# jkff_v8.net
KiCad netlist of a schematic drawn in EAGLE
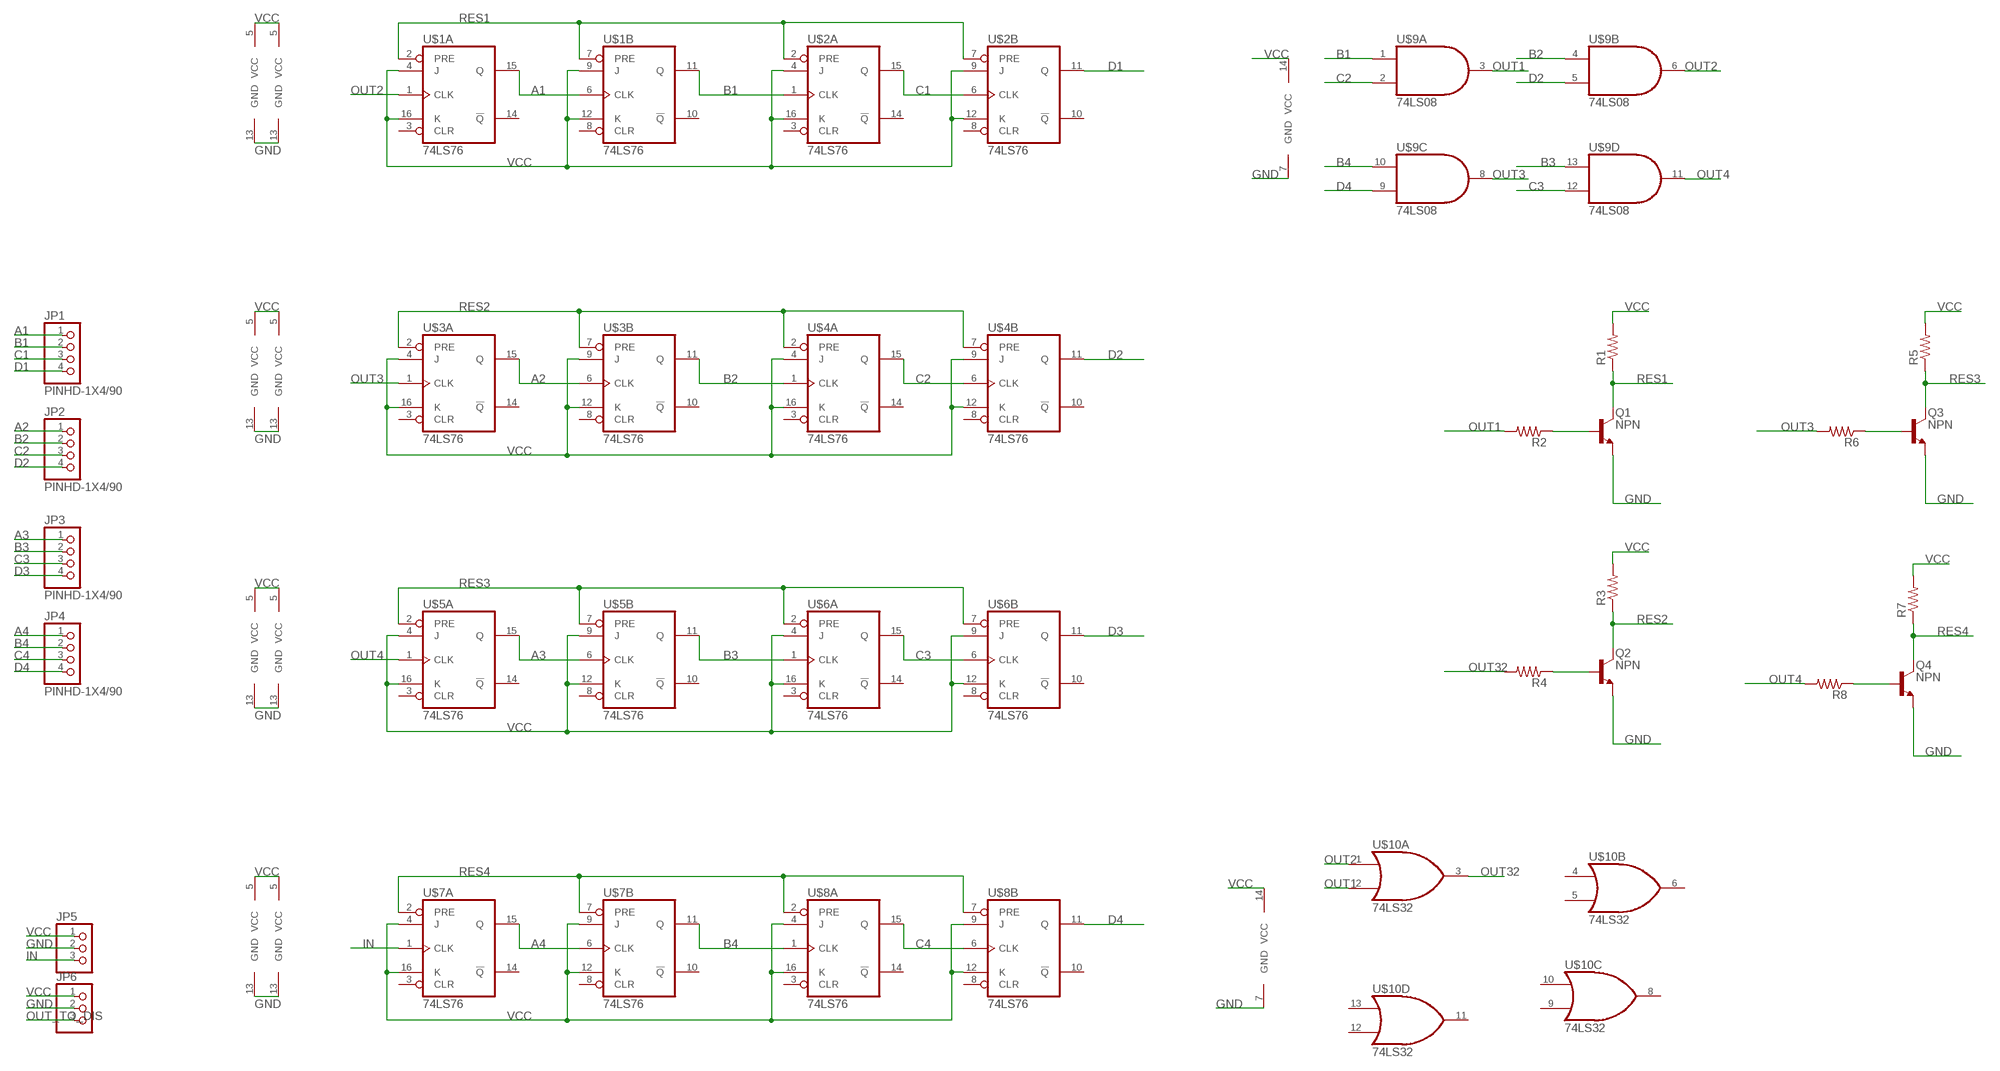
[diagram p0: schematic, sheet 1]

(export (version "E")
  (design (tool "Eeschema 10.0.6"))
  (components
    (comp (ref "JP1")
      (value "PINHD-1X4/90")
      (footprint "eagle-import:1X04_90")
      (libsource (lib "eagle-import") (part "PINHD-1X4/90"))
    )
    (comp (ref "JP2")
      (value "PINHD-1X4/90")
      (footprint "eagle-import:1X04_90")
      (libsource (lib "eagle-import") (part "PINHD-1X4/90"))
    )
    (comp (ref "JP3")
      (value "PINHD-1X4/90")
      (footprint "eagle-import:1X04_90")
      (libsource (lib "eagle-import") (part "PINHD-1X4/90"))
    )
    (comp (ref "JP4")
      (value "PINHD-1X4/90")
      (footprint "eagle-import:1X04_90")
      (libsource (lib "eagle-import") (part "PINHD-1X4/90"))
    )
    (comp (ref "JP5")
      (value "PINHD-1X3CB")
      (footprint "eagle-import:1X03-CLEANBIG")
      (libsource (lib "eagle-import") (part "PINHD-1X3CB"))
    )
    (comp (ref "JP6")
      (value "PINHD-1X3CB")
      (footprint "eagle-import:1X03-CLEANBIG")
      (libsource (lib "eagle-import") (part "PINHD-1X3CB"))
    )
    (comp (ref "Q1")
      (value "NPN")
      (footprint "eagle-import:TO92")
      (libsource (lib "eagle-import") (part "NPNTO92-EBC_"))
    )
    (comp (ref "Q2")
      (value "NPN")
      (footprint "eagle-import:TO92")
      (libsource (lib "eagle-import") (part "NPNTO92-EBC_"))
    )
    (comp (ref "Q3")
      (value "NPN")
      (footprint "eagle-import:TO92")
      (libsource (lib "eagle-import") (part "NPNTO92-EBC_"))
    )
    (comp (ref "Q4")
      (value "NPN")
      (footprint "eagle-import:TO92")
      (libsource (lib "eagle-import") (part "NPNTO92-EBC_"))
    )
    (comp (ref "R1")
      (value "R-US_AXIAL-7.2MM-PITCH")
      (footprint "eagle-import:RESAD724W46L381D178B")
      (libsource (lib "eagle-import") (part "R-USAXIAL-7.2MM-PITCH_"))
    )
    (comp (ref "R2")
      (value "R-US_AXIAL-7.2MM-PITCH")
      (footprint "eagle-import:RESAD724W46L381D178B")
      (libsource (lib "eagle-import") (part "R-USAXIAL-7.2MM-PITCH_"))
    )
    (comp (ref "R3")
      (value "R-US_AXIAL-7.2MM-PITCH")
      (footprint "eagle-import:RESAD724W46L381D178B")
      (libsource (lib "eagle-import") (part "R-USAXIAL-7.2MM-PITCH_"))
    )
    (comp (ref "R4")
      (value "R-US_AXIAL-7.2MM-PITCH")
      (footprint "eagle-import:RESAD724W46L381D178B")
      (libsource (lib "eagle-import") (part "R-USAXIAL-7.2MM-PITCH_"))
    )
    (comp (ref "R5")
      (value "R-US_AXIAL-7.2MM-PITCH")
      (footprint "eagle-import:RESAD724W46L381D178B")
      (libsource (lib "eagle-import") (part "R-USAXIAL-7.2MM-PITCH_"))
    )
    (comp (ref "R6")
      (value "R-US_AXIAL-7.2MM-PITCH")
      (footprint "eagle-import:RESAD724W46L381D178B")
      (libsource (lib "eagle-import") (part "R-USAXIAL-7.2MM-PITCH_"))
    )
    (comp (ref "R7")
      (value "R-US_AXIAL-7.2MM-PITCH")
      (footprint "eagle-import:RESAD724W46L381D178B")
      (libsource (lib "eagle-import") (part "R-USAXIAL-7.2MM-PITCH_"))
    )
    (comp (ref "R8")
      (value "R-US_AXIAL-7.2MM-PITCH")
      (footprint "eagle-import:RESAD724W46L381D178B")
      (libsource (lib "eagle-import") (part "R-USAXIAL-7.2MM-PITCH_"))
    )
    (comp (ref "U$1")
      (value "74LS76")
      (footprint "eagle-import:DIO16")
      (libsource (lib "eagle-import") (part "74LS76"))
    )
    (comp (ref "U$2")
      (value "74LS76")
      (footprint "eagle-import:DIO16")
      (libsource (lib "eagle-import") (part "74LS76"))
    )
    (comp (ref "U$3")
      (value "74LS76")
      (footprint "eagle-import:DIO16")
      (libsource (lib "eagle-import") (part "74LS76"))
    )
    (comp (ref "U$4")
      (value "74LS76")
      (footprint "eagle-import:DIO16")
      (libsource (lib "eagle-import") (part "74LS76"))
    )
    (comp (ref "U$5")
      (value "74LS76")
      (footprint "eagle-import:DIO16")
      (libsource (lib "eagle-import") (part "74LS76"))
    )
    (comp (ref "U$6")
      (value "74LS76")
      (footprint "eagle-import:DIO16")
      (libsource (lib "eagle-import") (part "74LS76"))
    )
    (comp (ref "U$7")
      (value "74LS76")
      (footprint "eagle-import:DIO16")
      (libsource (lib "eagle-import") (part "74LS76"))
    )
    (comp (ref "U$8")
      (value "74LS76")
      (footprint "eagle-import:DIO16")
      (libsource (lib "eagle-import") (part "74LS76"))
    )
    (comp (ref "U$9")
      (value "74LS08")
      (footprint "eagle-import:DIO14")
      (libsource (lib "eagle-import") (part "74LS08"))
    )
    (comp (ref "U$10")
      (value "74LS32")
      (footprint "eagle-import:DIO14")
      (libsource (lib "eagle-import") (part "74LS32"))
    )
  )
  (nets
    (net (code "1") (name "/A1") (class "Default")
      (node (ref "JP1") (pin "1") (pinfunction "1_1") (pintype "passive"))
      (node (ref "U$1") (pin "15") (pinfunction "Q_15") (pintype "output"))
      (node (ref "U$1") (pin "6") (pinfunction "CLK_6") (pintype "input"))
    )
    (net (code "2") (name "/A2") (class "Default")
      (node (ref "JP2") (pin "1") (pinfunction "1_1") (pintype "passive"))
      (node (ref "U$3") (pin "15") (pinfunction "Q_15") (pintype "output"))
      (node (ref "U$3") (pin "6") (pinfunction "CLK_6") (pintype "input"))
    )
    (net (code "3") (name "/A3") (class "Default")
      (node (ref "JP3") (pin "1") (pinfunction "1_1") (pintype "passive"))
      (node (ref "U$5") (pin "15") (pinfunction "Q_15") (pintype "output"))
      (node (ref "U$5") (pin "6") (pinfunction "CLK_6") (pintype "input"))
    )
    (net (code "4") (name "/A4") (class "Default")
      (node (ref "JP4") (pin "1") (pinfunction "1_1") (pintype "passive"))
      (node (ref "U$7") (pin "15") (pinfunction "Q_15") (pintype "output"))
      (node (ref "U$7") (pin "6") (pinfunction "CLK_6") (pintype "input"))
    )
    (net (code "5") (name "/B1") (class "Default")
      (node (ref "JP1") (pin "2") (pinfunction "2_2") (pintype "passive"))
      (node (ref "U$1") (pin "11") (pinfunction "Q_11") (pintype "output"))
      (node (ref "U$2") (pin "1") (pinfunction "CLK_1") (pintype "input"))
      (node (ref "U$9") (pin "1") (pinfunction "I0_1") (pintype "input"))
    )
    (net (code "6") (name "/B2") (class "Default")
      (node (ref "JP2") (pin "2") (pinfunction "2_2") (pintype "passive"))
      (node (ref "U$3") (pin "11") (pinfunction "Q_11") (pintype "output"))
      (node (ref "U$4") (pin "1") (pinfunction "CLK_1") (pintype "input"))
      (node (ref "U$9") (pin "4") (pinfunction "I0_4") (pintype "input"))
    )
    (net (code "7") (name "/B3") (class "Default")
      (node (ref "JP3") (pin "2") (pinfunction "2_2") (pintype "passive"))
      (node (ref "U$5") (pin "11") (pinfunction "Q_11") (pintype "output"))
      (node (ref "U$6") (pin "1") (pinfunction "CLK_1") (pintype "input"))
      (node (ref "U$9") (pin "13") (pinfunction "I0_13") (pintype "input"))
    )
    (net (code "8") (name "/B4") (class "Default")
      (node (ref "JP4") (pin "2") (pinfunction "2_2") (pintype "passive"))
      (node (ref "U$7") (pin "11") (pinfunction "Q_11") (pintype "output"))
      (node (ref "U$8") (pin "1") (pinfunction "CLK_1") (pintype "input"))
      (node (ref "U$9") (pin "10") (pinfunction "I0_10") (pintype "input"))
    )
    (net (code "9") (name "/C1") (class "Default")
      (node (ref "JP1") (pin "3") (pinfunction "3_3") (pintype "passive"))
      (node (ref "U$2") (pin "15") (pinfunction "Q_15") (pintype "output"))
      (node (ref "U$2") (pin "6") (pinfunction "CLK_6") (pintype "input"))
    )
    (net (code "10") (name "/C2") (class "Default")
      (node (ref "JP2") (pin "3") (pinfunction "3_3") (pintype "passive"))
      (node (ref "U$4") (pin "15") (pinfunction "Q_15") (pintype "output"))
      (node (ref "U$4") (pin "6") (pinfunction "CLK_6") (pintype "input"))
      (node (ref "U$9") (pin "2") (pinfunction "I1_2") (pintype "input"))
    )
    (net (code "11") (name "/C3") (class "Default")
      (node (ref "JP3") (pin "3") (pinfunction "3_3") (pintype "passive"))
      (node (ref "U$6") (pin "15") (pinfunction "Q_15") (pintype "output"))
      (node (ref "U$6") (pin "6") (pinfunction "CLK_6") (pintype "input"))
      (node (ref "U$9") (pin "12") (pinfunction "I1_12") (pintype "input"))
    )
    (net (code "12") (name "/C4") (class "Default")
      (node (ref "JP4") (pin "3") (pinfunction "3_3") (pintype "passive"))
      (node (ref "U$8") (pin "15") (pinfunction "Q_15") (pintype "output"))
      (node (ref "U$8") (pin "6") (pinfunction "CLK_6") (pintype "input"))
    )
    (net (code "13") (name "/D1") (class "Default")
      (node (ref "JP1") (pin "4") (pinfunction "4_4") (pintype "passive"))
      (node (ref "U$2") (pin "11") (pinfunction "Q_11") (pintype "output"))
    )
    (net (code "14") (name "/D2") (class "Default")
      (node (ref "JP2") (pin "4") (pinfunction "4_4") (pintype "passive"))
      (node (ref "U$4") (pin "11") (pinfunction "Q_11") (pintype "output"))
      (node (ref "U$9") (pin "5") (pinfunction "I1_5") (pintype "input"))
    )
    (net (code "15") (name "/D3") (class "Default")
      (node (ref "JP3") (pin "4") (pinfunction "4_4") (pintype "passive"))
      (node (ref "U$6") (pin "11") (pinfunction "Q_11") (pintype "output"))
    )
    (net (code "16") (name "/D4") (class "Default")
      (node (ref "JP4") (pin "4") (pinfunction "4_4") (pintype "passive"))
      (node (ref "U$8") (pin "11") (pinfunction "Q_11") (pintype "output"))
      (node (ref "U$9") (pin "9") (pinfunction "I1_9") (pintype "input"))
    )
    (net (code "17") (name "/GND") (class "Default")
      (node (ref "JP5") (pin "2") (pinfunction "2_2") (pintype "passive"))
      (node (ref "JP6") (pin "2") (pinfunction "2_2") (pintype "passive"))
      (node (ref "Q1") (pin "1") (pinfunction "E_1") (pintype "passive"))
      (node (ref "Q2") (pin "1") (pinfunction "E_1") (pintype "passive"))
      (node (ref "Q3") (pin "1") (pinfunction "E_1") (pintype "passive"))
      (node (ref "Q4") (pin "1") (pinfunction "E_1") (pintype "passive"))
      (node (ref "U$1") (pin "13") (pinfunction "GND_13") (pintype "bidirectional"))
      (node (ref "U$10") (pin "7") (pinfunction "GND_7") (pintype "bidirectional"))
      (node (ref "U$2") (pin "13") (pinfunction "GND_13") (pintype "bidirectional"))
      (node (ref "U$3") (pin "13") (pinfunction "GND_13") (pintype "bidirectional"))
      (node (ref "U$4") (pin "13") (pinfunction "GND_13") (pintype "bidirectional"))
      (node (ref "U$5") (pin "13") (pinfunction "GND_13") (pintype "bidirectional"))
      (node (ref "U$6") (pin "13") (pinfunction "GND_13") (pintype "bidirectional"))
      (node (ref "U$7") (pin "13") (pinfunction "GND_13") (pintype "bidirectional"))
      (node (ref "U$8") (pin "13") (pinfunction "GND_13") (pintype "bidirectional"))
      (node (ref "U$9") (pin "7") (pinfunction "GND_7") (pintype "bidirectional"))
    )
    (net (code "18") (name "/IN") (class "Default")
      (node (ref "JP5") (pin "3") (pinfunction "3_3") (pintype "passive"))
      (node (ref "U$7") (pin "1") (pinfunction "CLK_1") (pintype "input"))
    )
    (net (code "19") (name "/OUT1") (class "Default")
      (node (ref "R2") (pin "2") (pinfunction "2_2") (pintype "passive"))
      (node (ref "U$10") (pin "2") (pinfunction "I1_2") (pintype "input"))
      (node (ref "U$9") (pin "3") (pinfunction "O_3") (pintype "output"))
    )
    (net (code "20") (name "/OUT2") (class "Default")
      (node (ref "U$1") (pin "1") (pinfunction "CLK_1") (pintype "input"))
      (node (ref "U$10") (pin "1") (pinfunction "I0_1") (pintype "input"))
      (node (ref "U$9") (pin "6") (pinfunction "O_6") (pintype "output"))
    )
    (net (code "21") (name "/OUT3") (class "Default")
      (node (ref "R6") (pin "2") (pinfunction "2_2") (pintype "passive"))
      (node (ref "U$3") (pin "1") (pinfunction "CLK_1") (pintype "input"))
      (node (ref "U$9") (pin "8") (pinfunction "O_8") (pintype "output"))
    )
    (net (code "22") (name "/OUT4") (class "Default")
      (node (ref "R8") (pin "2") (pinfunction "2_2") (pintype "passive"))
      (node (ref "U$5") (pin "1") (pinfunction "CLK_1") (pintype "input"))
      (node (ref "U$9") (pin "11") (pinfunction "O_11") (pintype "output"))
    )
    (net (code "23") (name "/OUT32") (class "Default")
      (node (ref "R4") (pin "2") (pinfunction "2_2") (pintype "passive"))
      (node (ref "U$10") (pin "3") (pinfunction "O_3") (pintype "output"))
    )
    (net (code "24") (name "/OUT_TO_DIS") (class "Default")
      (node (ref "JP6") (pin "3") (pinfunction "3_3") (pintype "passive"))
    )
    (net (code "25") (name "/RES1") (class "Default")
      (node (ref "Q1") (pin "3") (pinfunction "C_3") (pintype "passive"))
      (node (ref "R1") (pin "1") (pinfunction "1_1") (pintype "passive"))
      (node (ref "U$1") (pin "2") (pinfunction "PRE_2") (pintype "input"))
      (node (ref "U$1") (pin "7") (pinfunction "PRE_7") (pintype "input"))
      (node (ref "U$2") (pin "2") (pinfunction "PRE_2") (pintype "input"))
      (node (ref "U$2") (pin "7") (pinfunction "PRE_7") (pintype "input"))
    )
    (net (code "26") (name "/RES2") (class "Default")
      (node (ref "Q2") (pin "3") (pinfunction "C_3") (pintype "passive"))
      (node (ref "R3") (pin "1") (pinfunction "1_1") (pintype "passive"))
      (node (ref "U$3") (pin "2") (pinfunction "PRE_2") (pintype "input"))
      (node (ref "U$3") (pin "7") (pinfunction "PRE_7") (pintype "input"))
      (node (ref "U$4") (pin "2") (pinfunction "PRE_2") (pintype "input"))
      (node (ref "U$4") (pin "7") (pinfunction "PRE_7") (pintype "input"))
    )
    (net (code "27") (name "/RES3") (class "Default")
      (node (ref "Q3") (pin "3") (pinfunction "C_3") (pintype "passive"))
      (node (ref "R5") (pin "1") (pinfunction "1_1") (pintype "passive"))
      (node (ref "U$5") (pin "2") (pinfunction "PRE_2") (pintype "input"))
      (node (ref "U$5") (pin "7") (pinfunction "PRE_7") (pintype "input"))
      (node (ref "U$6") (pin "2") (pinfunction "PRE_2") (pintype "input"))
      (node (ref "U$6") (pin "7") (pinfunction "PRE_7") (pintype "input"))
    )
    (net (code "28") (name "/RES4") (class "Default")
      (node (ref "Q4") (pin "3") (pinfunction "C_3") (pintype "passive"))
      (node (ref "R7") (pin "1") (pinfunction "1_1") (pintype "passive"))
      (node (ref "U$7") (pin "2") (pinfunction "PRE_2") (pintype "input"))
      (node (ref "U$7") (pin "7") (pinfunction "PRE_7") (pintype "input"))
      (node (ref "U$8") (pin "2") (pinfunction "PRE_2") (pintype "input"))
      (node (ref "U$8") (pin "7") (pinfunction "PRE_7") (pintype "input"))
    )
    (net (code "29") (name "/VCC") (class "Default")
      (node (ref "JP5") (pin "1") (pinfunction "1_1") (pintype "passive"))
      (node (ref "JP6") (pin "1") (pinfunction "1_1") (pintype "passive"))
      (node (ref "R1") (pin "2") (pinfunction "2_2") (pintype "passive"))
      (node (ref "R3") (pin "2") (pinfunction "2_2") (pintype "passive"))
      (node (ref "R5") (pin "2") (pinfunction "2_2") (pintype "passive"))
      (node (ref "R7") (pin "2") (pinfunction "2_2") (pintype "passive"))
      (node (ref "U$1") (pin "12") (pinfunction "K_12") (pintype "input"))
      (node (ref "U$1") (pin "16") (pinfunction "K_16") (pintype "input"))
      (node (ref "U$1") (pin "4") (pinfunction "J_4") (pintype "input"))
      (node (ref "U$1") (pin "5") (pinfunction "VCC_5") (pintype "bidirectional"))
      (node (ref "U$1") (pin "9") (pinfunction "J_9") (pintype "input"))
      (node (ref "U$10") (pin "14") (pinfunction "VCC_14") (pintype "bidirectional"))
      (node (ref "U$2") (pin "12") (pinfunction "K_12") (pintype "input"))
      (node (ref "U$2") (pin "16") (pinfunction "K_16") (pintype "input"))
      (node (ref "U$2") (pin "4") (pinfunction "J_4") (pintype "input"))
      (node (ref "U$2") (pin "5") (pinfunction "VCC_5") (pintype "bidirectional"))
      (node (ref "U$2") (pin "9") (pinfunction "J_9") (pintype "input"))
      (node (ref "U$3") (pin "12") (pinfunction "K_12") (pintype "input"))
      (node (ref "U$3") (pin "16") (pinfunction "K_16") (pintype "input"))
      (node (ref "U$3") (pin "4") (pinfunction "J_4") (pintype "input"))
      (node (ref "U$3") (pin "5") (pinfunction "VCC_5") (pintype "bidirectional"))
      (node (ref "U$3") (pin "9") (pinfunction "J_9") (pintype "input"))
      (node (ref "U$4") (pin "12") (pinfunction "K_12") (pintype "input"))
      (node (ref "U$4") (pin "16") (pinfunction "K_16") (pintype "input"))
      (node (ref "U$4") (pin "4") (pinfunction "J_4") (pintype "input"))
      (node (ref "U$4") (pin "5") (pinfunction "VCC_5") (pintype "bidirectional"))
      (node (ref "U$4") (pin "9") (pinfunction "J_9") (pintype "input"))
      (node (ref "U$5") (pin "12") (pinfunction "K_12") (pintype "input"))
      (node (ref "U$5") (pin "16") (pinfunction "K_16") (pintype "input"))
      (node (ref "U$5") (pin "4") (pinfunction "J_4") (pintype "input"))
      (node (ref "U$5") (pin "5") (pinfunction "VCC_5") (pintype "bidirectional"))
      (node (ref "U$5") (pin "9") (pinfunction "J_9") (pintype "input"))
      (node (ref "U$6") (pin "12") (pinfunction "K_12") (pintype "input"))
      (node (ref "U$6") (pin "16") (pinfunction "K_16") (pintype "input"))
      (node (ref "U$6") (pin "4") (pinfunction "J_4") (pintype "input"))
      (node (ref "U$6") (pin "5") (pinfunction "VCC_5") (pintype "bidirectional"))
      (node (ref "U$6") (pin "9") (pinfunction "J_9") (pintype "input"))
      (node (ref "U$7") (pin "12") (pinfunction "K_12") (pintype "input"))
      (node (ref "U$7") (pin "16") (pinfunction "K_16") (pintype "input"))
      (node (ref "U$7") (pin "4") (pinfunction "J_4") (pintype "input"))
      (node (ref "U$7") (pin "5") (pinfunction "VCC_5") (pintype "bidirectional"))
      (node (ref "U$7") (pin "9") (pinfunction "J_9") (pintype "input"))
      (node (ref "U$8") (pin "12") (pinfunction "K_12") (pintype "input"))
      (node (ref "U$8") (pin "16") (pinfunction "K_16") (pintype "input"))
      (node (ref "U$8") (pin "4") (pinfunction "J_4") (pintype "input"))
      (node (ref "U$8") (pin "5") (pinfunction "VCC_5") (pintype "bidirectional"))
      (node (ref "U$8") (pin "9") (pinfunction "J_9") (pintype "input"))
      (node (ref "U$9") (pin "14") (pinfunction "VCC_14") (pintype "bidirectional"))
    )
    (net (code "30") (name "Net-(Q1-B)") (class "Default")
      (node (ref "Q1") (pin "2") (pinfunction "B_2") (pintype "passive"))
      (node (ref "R2") (pin "1") (pinfunction "1_1") (pintype "passive"))
    )
    (net (code "31") (name "Net-(Q2-B)") (class "Default")
      (node (ref "Q2") (pin "2") (pinfunction "B_2") (pintype "passive"))
      (node (ref "R4") (pin "1") (pinfunction "1_1") (pintype "passive"))
    )
    (net (code "32") (name "Net-(Q3-B)") (class "Default")
      (node (ref "Q3") (pin "2") (pinfunction "B_2") (pintype "passive"))
      (node (ref "R6") (pin "1") (pinfunction "1_1") (pintype "passive"))
    )
    (net (code "33") (name "Net-(Q4-B)") (class "Default")
      (node (ref "Q4") (pin "2") (pinfunction "B_2") (pintype "passive"))
      (node (ref "R8") (pin "1") (pinfunction "1_1") (pintype "passive"))
    )
    (net (code "34") (name "unconnected-(U$1A-CLR-Pad3)") (class "Default")
      (node (ref "U$1") (pin "3") (pinfunction "CLR_3") (pintype "input"))
    )
    (net (code "35") (name "unconnected-(U$1A-~{Q}-Pad14)") (class "Default")
      (node (ref "U$1") (pin "14") (pinfunction "~{Q}_14") (pintype "output"))
    )
    (net (code "36") (name "unconnected-(U$1B-CLR-Pad8)") (class "Default")
      (node (ref "U$1") (pin "8") (pinfunction "CLR_8") (pintype "input"))
    )
    (net (code "37") (name "unconnected-(U$1B-~{Q}-Pad10)") (class "Default")
      (node (ref "U$1") (pin "10") (pinfunction "~{Q}_10") (pintype "output"))
    )
    (net (code "38") (name "unconnected-(U$2A-CLR-Pad3)") (class "Default")
      (node (ref "U$2") (pin "3") (pinfunction "CLR_3") (pintype "input"))
    )
    (net (code "39") (name "unconnected-(U$2A-~{Q}-Pad14)") (class "Default")
      (node (ref "U$2") (pin "14") (pinfunction "~{Q}_14") (pintype "output"))
    )
    (net (code "40") (name "unconnected-(U$2B-CLR-Pad8)") (class "Default")
      (node (ref "U$2") (pin "8") (pinfunction "CLR_8") (pintype "input"))
    )
    (net (code "41") (name "unconnected-(U$2B-~{Q}-Pad10)") (class "Default")
      (node (ref "U$2") (pin "10") (pinfunction "~{Q}_10") (pintype "output"))
    )
    (net (code "42") (name "unconnected-(U$3A-CLR-Pad3)") (class "Default")
      (node (ref "U$3") (pin "3") (pinfunction "CLR_3") (pintype "input"))
    )
    (net (code "43") (name "unconnected-(U$3A-~{Q}-Pad14)") (class "Default")
      (node (ref "U$3") (pin "14") (pinfunction "~{Q}_14") (pintype "output"))
    )
    (net (code "44") (name "unconnected-(U$3B-CLR-Pad8)") (class "Default")
      (node (ref "U$3") (pin "8") (pinfunction "CLR_8") (pintype "input"))
    )
    (net (code "45") (name "unconnected-(U$3B-~{Q}-Pad10)") (class "Default")
      (node (ref "U$3") (pin "10") (pinfunction "~{Q}_10") (pintype "output"))
    )
    (net (code "46") (name "unconnected-(U$4A-CLR-Pad3)") (class "Default")
      (node (ref "U$4") (pin "3") (pinfunction "CLR_3") (pintype "input"))
    )
    (net (code "47") (name "unconnected-(U$4A-~{Q}-Pad14)") (class "Default")
      (node (ref "U$4") (pin "14") (pinfunction "~{Q}_14") (pintype "output"))
    )
    (net (code "48") (name "unconnected-(U$4B-CLR-Pad8)") (class "Default")
      (node (ref "U$4") (pin "8") (pinfunction "CLR_8") (pintype "input"))
    )
    (net (code "49") (name "unconnected-(U$4B-~{Q}-Pad10)") (class "Default")
      (node (ref "U$4") (pin "10") (pinfunction "~{Q}_10") (pintype "output"))
    )
    (net (code "50") (name "unconnected-(U$5A-CLR-Pad3)") (class "Default")
      (node (ref "U$5") (pin "3") (pinfunction "CLR_3") (pintype "input"))
    )
    (net (code "51") (name "unconnected-(U$5A-~{Q}-Pad14)") (class "Default")
      (node (ref "U$5") (pin "14") (pinfunction "~{Q}_14") (pintype "output"))
    )
    (net (code "52") (name "unconnected-(U$5B-CLR-Pad8)") (class "Default")
      (node (ref "U$5") (pin "8") (pinfunction "CLR_8") (pintype "input"))
    )
    (net (code "53") (name "unconnected-(U$5B-~{Q}-Pad10)") (class "Default")
      (node (ref "U$5") (pin "10") (pinfunction "~{Q}_10") (pintype "output"))
    )
    (net (code "54") (name "unconnected-(U$6A-CLR-Pad3)") (class "Default")
      (node (ref "U$6") (pin "3") (pinfunction "CLR_3") (pintype "input"))
    )
    (net (code "55") (name "unconnected-(U$6A-~{Q}-Pad14)") (class "Default")
      (node (ref "U$6") (pin "14") (pinfunction "~{Q}_14") (pintype "output"))
    )
    (net (code "56") (name "unconnected-(U$6B-CLR-Pad8)") (class "Default")
      (node (ref "U$6") (pin "8") (pinfunction "CLR_8") (pintype "input"))
    )
    (net (code "57") (name "unconnected-(U$6B-~{Q}-Pad10)") (class "Default")
      (node (ref "U$6") (pin "10") (pinfunction "~{Q}_10") (pintype "output"))
    )
    (net (code "58") (name "unconnected-(U$7A-CLR-Pad3)") (class "Default")
      (node (ref "U$7") (pin "3") (pinfunction "CLR_3") (pintype "input"))
    )
    (net (code "59") (name "unconnected-(U$7A-~{Q}-Pad14)") (class "Default")
      (node (ref "U$7") (pin "14") (pinfunction "~{Q}_14") (pintype "output"))
    )
    (net (code "60") (name "unconnected-(U$7B-CLR-Pad8)") (class "Default")
      (node (ref "U$7") (pin "8") (pinfunction "CLR_8") (pintype "input"))
    )
    (net (code "61") (name "unconnected-(U$7B-~{Q}-Pad10)") (class "Default")
      (node (ref "U$7") (pin "10") (pinfunction "~{Q}_10") (pintype "output"))
    )
    (net (code "62") (name "unconnected-(U$8A-CLR-Pad3)") (class "Default")
      (node (ref "U$8") (pin "3") (pinfunction "CLR_3") (pintype "input"))
    )
    (net (code "63") (name "unconnected-(U$8A-~{Q}-Pad14)") (class "Default")
      (node (ref "U$8") (pin "14") (pinfunction "~{Q}_14") (pintype "output"))
    )
    (net (code "64") (name "unconnected-(U$8B-CLR-Pad8)") (class "Default")
      (node (ref "U$8") (pin "8") (pinfunction "CLR_8") (pintype "input"))
    )
    (net (code "65") (name "unconnected-(U$8B-~{Q}-Pad10)") (class "Default")
      (node (ref "U$8") (pin "10") (pinfunction "~{Q}_10") (pintype "output"))
    )
    (net (code "66") (name "unconnected-(U$10B-I0-Pad4)") (class "Default")
      (node (ref "U$10") (pin "4") (pinfunction "I0_4") (pintype "input"))
    )
    (net (code "67") (name "unconnected-(U$10B-I1-Pad5)") (class "Default")
      (node (ref "U$10") (pin "5") (pinfunction "I1_5") (pintype "input"))
    )
    (net (code "68") (name "unconnected-(U$10B-O-Pad6)") (class "Default")
      (node (ref "U$10") (pin "6") (pinfunction "O_6") (pintype "output"))
    )
    (net (code "69") (name "unconnected-(U$10C-I0-Pad10)") (class "Default")
      (node (ref "U$10") (pin "10") (pinfunction "I0_10") (pintype "input"))
    )
    (net (code "70") (name "unconnected-(U$10C-I1-Pad9)") (class "Default")
      (node (ref "U$10") (pin "9") (pinfunction "I1_9") (pintype "input"))
    )
    (net (code "71") (name "unconnected-(U$10C-O-Pad8)") (class "Default")
      (node (ref "U$10") (pin "8") (pinfunction "O_8") (pintype "output"))
    )
    (net (code "72") (name "unconnected-(U$10D-I0-Pad13)") (class "Default")
      (node (ref "U$10") (pin "13") (pinfunction "I0_13") (pintype "input"))
    )
    (net (code "73") (name "unconnected-(U$10D-I1-Pad12)") (class "Default")
      (node (ref "U$10") (pin "12") (pinfunction "I1_12") (pintype "input"))
    )
    (net (code "74") (name "unconnected-(U$10D-O-Pad11)") (class "Default")
      (node (ref "U$10") (pin "11") (pinfunction "O_11") (pintype "output"))
    )
  )
)
